# SkyKontrol-datalogger.net
KiCad netlist of a schematic drawn in EAGLE
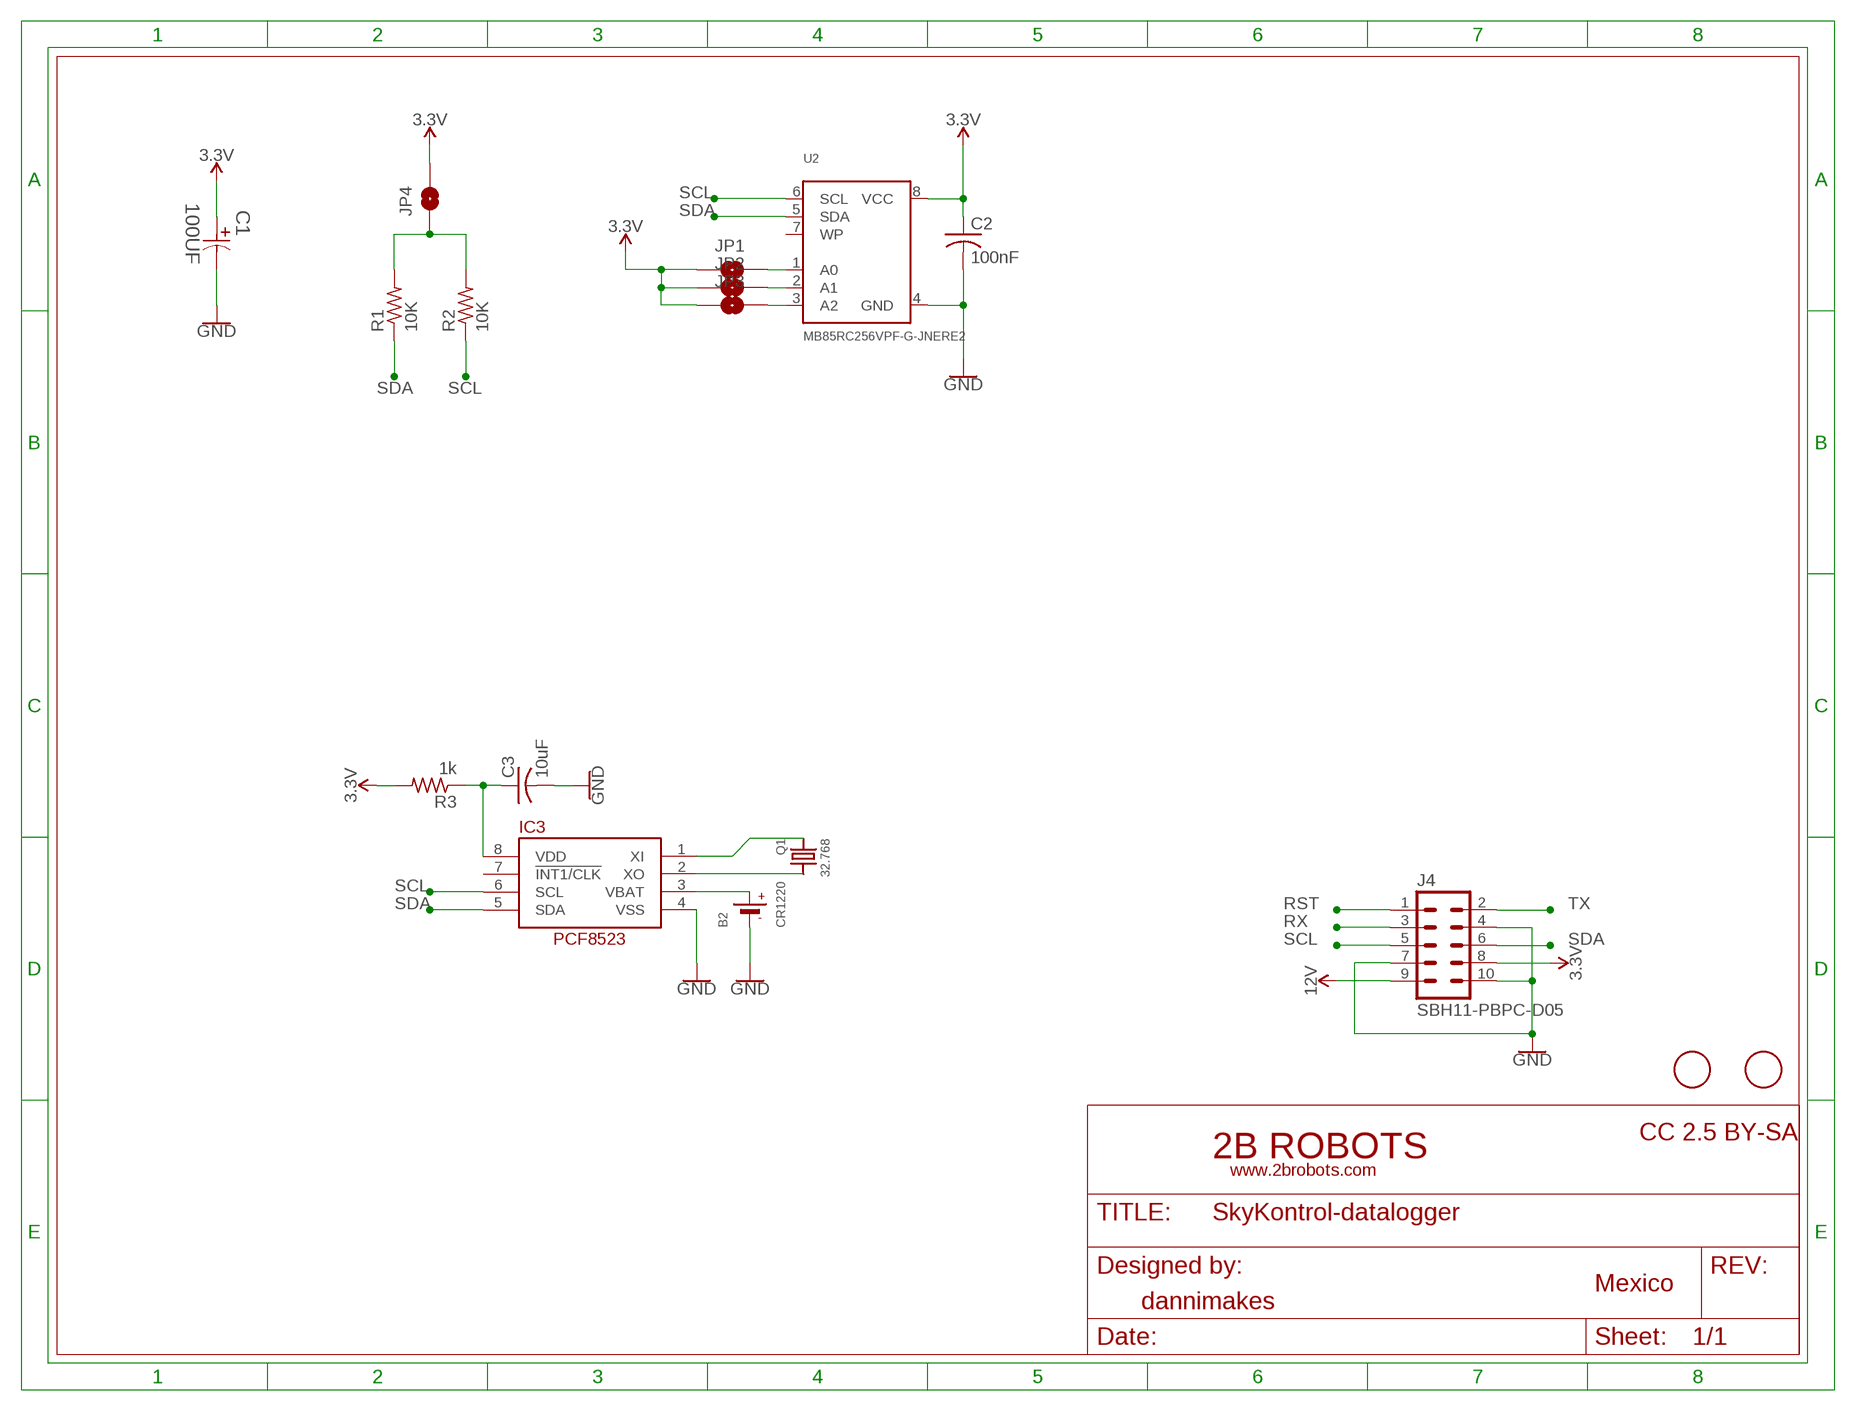
[diagram p0: schematic, sheet 1]

(export (version "E")
  (design (tool "Eeschema 10.0.6"))
  (components
    (comp (ref "B2")
      (value "CR1220")
      (footprint "eagle-import:CR1220")
      (libsource (lib "eagle-import") (part "BATTERYCR1220_SMT"))
    )
    (comp (ref "C1")
      (value "100UF")
      (footprint "eagle-import:CAPAE660X800N")
      (fields (field (name "MPN") "EEE-HA1E101XP") (field (name "TOLERANCE") "±20 %"))
      (libsource (lib "eagle-import") (part "EEE--CASE-D8HA1E101XP"))
    )
    (comp (ref "C2")
      (value "100nF")
      (footprint "eagle-import:C0603K")
      (libsource (lib "eagle-import") (part "C-USC0603K"))
    )
    (comp (ref "C3")
      (value "10uF")
      (footprint "eagle-import:C0805K")
      (libsource (lib "eagle-import") (part "C-USC0805K"))
    )
    (comp (ref "IC3")
      (value "RTC_PCF8523T")
      (footprint "eagle-import:SOIC8_150MIL")
      (libsource (lib "eagle-import") (part "RTC_PCF8523T"))
    )
    (comp (ref "J4")
      (value "SBH11-PBPC-D05")
      (footprint "eagle-import:SBH11-PBPC-D05")
      (libsource (lib "eagle-import") (part "SBH11-PBPC-D05"))
    )
    (comp (ref "JP1")
      (value "JUMPER-SMT_2_NO_SILK")
      (footprint "eagle-import:SMT-JUMPER_2_NO_SILK")
      (libsource (lib "eagle-import") (part "JUMPER-SMT_2_NO_SILK"))
    )
    (comp (ref "JP2")
      (value "JUMPER-SMT_2_NO_SILK")
      (footprint "eagle-import:SMT-JUMPER_2_NO_SILK")
      (libsource (lib "eagle-import") (part "JUMPER-SMT_2_NO_SILK"))
    )
    (comp (ref "JP3")
      (value "JUMPER-SMT_2_NO_SILK")
      (footprint "eagle-import:SMT-JUMPER_2_NO_SILK")
      (libsource (lib "eagle-import") (part "JUMPER-SMT_2_NO_SILK"))
    )
    (comp (ref "JP4")
      (value "JUMPER-SMT_2_NO_SILK")
      (footprint "eagle-import:SMT-JUMPER_2_NO_SILK")
      (libsource (lib "eagle-import") (part "JUMPER-SMT_2_NO_SILK"))
    )
    (comp (ref "Q1")
      (value "32.768")
      (footprint "eagle-import:CRYSTAL_8X3.8")
      (libsource (lib "eagle-import") (part "CRYSTAL8.0X3.8"))
    )
    (comp (ref "R1")
      (value "10K")
      (footprint "eagle-import:R0805")
      (libsource (lib "eagle-import") (part "R-US_R0805"))
    )
    (comp (ref "R2")
      (value "10K")
      (footprint "eagle-import:R0805")
      (libsource (lib "eagle-import") (part "R-US_R0805"))
    )
    (comp (ref "R3")
      (value "1k")
      (footprint "eagle-import:R0805")
      (libsource (lib "eagle-import") (part "R-US_R0805"))
    )
    (comp (ref "U$1")
      (value "FIDUCIAL")
      (footprint "eagle-import:FIDUCIAL_1MM")
      (libsource (lib "eagle-import") (part "FIDUCIAL"))
    )
    (comp (ref "U$3")
      (value "FIDUCIAL")
      (footprint "eagle-import:FIDUCIAL_1MM")
      (libsource (lib "eagle-import") (part "FIDUCIAL"))
    )
    (comp (ref "U2")
      (value "MB85RC256VPF-G-JNERE2")
      (footprint "eagle-import:SOIC8_208MIL")
      (libsource (lib "eagle-import") (part "FRAM_SOIC8_I2C"))
    )
  )
  (nets
    (net (code "1") (name "/RST") (class "Default")
      (node (ref "J4") (pin "1") (pinfunction "1_1") (pintype "passive"))
    )
    (net (code "2") (name "/RX") (class "Default")
      (node (ref "J4") (pin "3") (pinfunction "3_3") (pintype "passive"))
    )
    (net (code "3") (name "/SCL") (class "Default")
      (node (ref "IC3") (pin "6") (pinfunction "SCL_6") (pintype "bidirectional"))
      (node (ref "J4") (pin "5") (pinfunction "5_5") (pintype "passive"))
      (node (ref "R2") (pin "1") (pinfunction "1_1") (pintype "passive"))
      (node (ref "U2") (pin "6") (pinfunction "SCL_6") (pintype "input"))
    )
    (net (code "4") (name "/SDA") (class "Default")
      (node (ref "IC3") (pin "5") (pinfunction "SDA_5") (pintype "bidirectional"))
      (node (ref "J4") (pin "6") (pinfunction "6_6") (pintype "passive"))
      (node (ref "R1") (pin "1") (pinfunction "1_1") (pintype "passive"))
      (node (ref "U2") (pin "5") (pinfunction "SDA_5") (pintype "bidirectional"))
    )
    (net (code "5") (name "/TX") (class "Default")
      (node (ref "J4") (pin "2") (pinfunction "2_2") (pintype "passive"))
    )
    (net (code "6") (name "3.3V") (class "Default")
      (node (ref "C1") (pin "1") (pinfunction "1_1") (pintype "passive"))
      (node (ref "C2") (pin "1") (pinfunction "1_1") (pintype "passive"))
      (node (ref "J4") (pin "8") (pinfunction "8_8") (pintype "passive"))
      (node (ref "JP1") (pin "1") (pinfunction "1_1") (pintype "passive"))
      (node (ref "JP2") (pin "1") (pinfunction "1_1") (pintype "passive"))
      (node (ref "JP3") (pin "1") (pinfunction "1_1") (pintype "passive"))
      (node (ref "JP4") (pin "2") (pinfunction "2_2") (pintype "passive"))
      (node (ref "R3") (pin "2") (pinfunction "2_2") (pintype "passive"))
      (node (ref "U2") (pin "8") (pinfunction "VCC_8") (pintype "power_in"))
    )
    (net (code "7") (name "12V") (class "Default")
      (node (ref "J4") (pin "9") (pinfunction "9_9") (pintype "passive"))
    )
    (net (code "8") (name "GND") (class "Default")
      (node (ref "B2") (pin "-") (pinfunction "-_-") (pintype "passive"))
      (node (ref "C1") (pin "2") (pinfunction "2_2") (pintype "passive"))
      (node (ref "C2") (pin "2") (pinfunction "2_2") (pintype "passive"))
      (node (ref "C3") (pin "2") (pinfunction "2_2") (pintype "passive"))
      (node (ref "IC3") (pin "4") (pinfunction "VSS_4") (pintype "power_in"))
      (node (ref "J4") (pin "10") (pinfunction "10_10") (pintype "passive"))
      (node (ref "J4") (pin "4") (pinfunction "4_4") (pintype "passive"))
      (node (ref "J4") (pin "7") (pinfunction "7_7") (pintype "passive"))
      (node (ref "U2") (pin "4") (pinfunction "GND_4") (pintype "power_in"))
    )
    (net (code "9") (name "Net-(B2-+)") (class "Default")
      (node (ref "B2") (pin "+$1") (pinfunction "+_+$1") (pintype "passive"))
      (node (ref "IC3") (pin "3") (pinfunction "VBAT_3") (pintype "power_in"))
    )
    (net (code "10") (name "Net-(IC3-VDD)") (class "Default")
      (node (ref "C3") (pin "1") (pinfunction "1_1") (pintype "passive"))
      (node (ref "IC3") (pin "8") (pinfunction "VDD_8") (pintype "power_in"))
      (node (ref "R3") (pin "1") (pinfunction "1_1") (pintype "passive"))
    )
    (net (code "11") (name "Net-(IC3-XI)") (class "Default")
      (node (ref "IC3") (pin "1") (pinfunction "XI_1") (pintype "input"))
      (node (ref "Q1") (pin "P$1") (pinfunction "1_P$1") (pintype "passive"))
    )
    (net (code "12") (name "Net-(IC3-XO)") (class "Default")
      (node (ref "IC3") (pin "2") (pinfunction "XO_2") (pintype "output"))
      (node (ref "Q1") (pin "P$4") (pinfunction "2_P$4") (pintype "passive"))
    )
    (net (code "13") (name "Net-(JP4-Pad1)") (class "Default")
      (node (ref "JP4") (pin "1") (pinfunction "1_1") (pintype "passive"))
      (node (ref "R1") (pin "2") (pinfunction "2_2") (pintype "passive"))
      (node (ref "R2") (pin "2") (pinfunction "2_2") (pintype "passive"))
    )
    (net (code "14") (name "Net-(U2-A0)") (class "Default")
      (node (ref "JP1") (pin "2") (pinfunction "2_2") (pintype "passive"))
      (node (ref "U2") (pin "1") (pinfunction "A0_1") (pintype "input"))
    )
    (net (code "15") (name "Net-(U2-A1)") (class "Default")
      (node (ref "JP2") (pin "2") (pinfunction "2_2") (pintype "passive"))
      (node (ref "U2") (pin "2") (pinfunction "A1_2") (pintype "input"))
    )
    (net (code "16") (name "Net-(U2-A2)") (class "Default")
      (node (ref "JP3") (pin "2") (pinfunction "2_2") (pintype "passive"))
      (node (ref "U2") (pin "3") (pinfunction "A2_3") (pintype "input"))
    )
    (net (code "17") (name "unconnected-(IC3-~{INT1{slash}CLK}-Pad7)") (class "Default")
      (node (ref "IC3") (pin "7") (pinfunction "~{INT1/CLK}_7") (pintype "output"))
    )
    (net (code "18") (name "unconnected-(U2-WP-Pad7)") (class "Default")
      (node (ref "U2") (pin "7") (pinfunction "WP_7") (pintype "input"))
    )
  )
)
